# D1_-_No_LCD.net
KiCad netlist of a schematic drawn in EAGLE
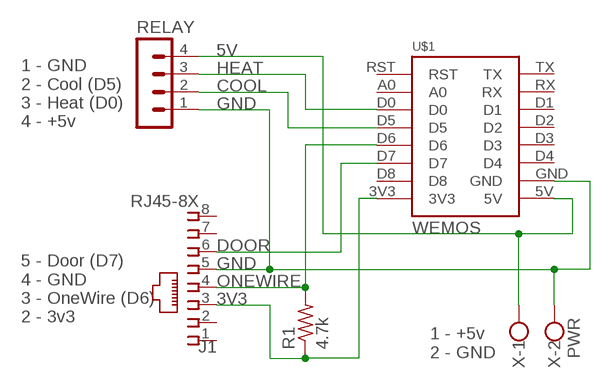
[diagram p0: schematic, sheet 1]

(export (version "E")
  (design (tool "Eeschema 10.0.6"))
  (components
    (comp (ref "J1")
      (value "RJ45-8X")
      (footprint "eagle-import:RJ45-NO-SHIELD")
      (libsource (lib "eagle-import") (part "RJ45-8X"))
    )
    (comp (ref "R1")
      (value "4.7k")
      (footprint "eagle-import:0309_12")
      (libsource (lib "eagle-import") (part "R-US_0309/12"))
    )
    (comp (ref "RELAY")
      (value "MA04-1")
      (footprint "eagle-import:MA04-1")
      (libsource (lib "eagle-import") (part "MA04-1"))
    )
    (comp (ref "U$1")
      (value "WEMOS")
      (footprint "eagle-import:WEMOS")
      (libsource (lib "eagle-import") (part "WEMOS"))
    )
    (comp (ref "X")
      (value "PWR")
      (footprint "eagle-import:W237-102")
      (fields (field (name "MPN") "237-102"))
      (libsource (lib "eagle-import") (part "W237-102"))
    )
  )
  (nets
    (net (code "1") (name "/3V3") (class "Default")
      (node (ref "J1") (pin "3") (pinfunction "3_3") (pintype "passive"))
      (node (ref "R1") (pin "1") (pinfunction "1_1") (pintype "passive"))
      (node (ref "U$1") (pin "3V3") (pinfunction "3V3_3V3") (pintype "bidirectional"))
    )
    (net (code "2") (name "/5V") (class "Default")
      (node (ref "RELAY") (pin "4") (pinfunction "4_4") (pintype "passive"))
      (node (ref "U$1") (pin "5V") (pinfunction "5V_5V") (pintype "bidirectional"))
      (node (ref "X") (pin "1") (pinfunction "KL_1") (pintype "passive"))
    )
    (net (code "3") (name "/COOL") (class "Default")
      (node (ref "RELAY") (pin "2") (pinfunction "2_2") (pintype "passive"))
      (node (ref "U$1") (pin "D5") (pinfunction "D5_D5") (pintype "bidirectional"))
    )
    (net (code "4") (name "/DOOR") (class "Default")
      (node (ref "J1") (pin "6") (pinfunction "6_6") (pintype "passive"))
      (node (ref "U$1") (pin "D7") (pinfunction "D7_D7") (pintype "bidirectional"))
    )
    (net (code "5") (name "/GND") (class "Default")
      (node (ref "J1") (pin "5") (pinfunction "5_5") (pintype "passive"))
      (node (ref "RELAY") (pin "1") (pinfunction "1_1") (pintype "passive"))
      (node (ref "U$1") (pin "GND") (pinfunction "GND_GND") (pintype "bidirectional"))
      (node (ref "X") (pin "2") (pinfunction "KL_2") (pintype "passive"))
    )
    (net (code "6") (name "/HEAT") (class "Default")
      (node (ref "RELAY") (pin "3") (pinfunction "3_3") (pintype "passive"))
      (node (ref "U$1") (pin "D0") (pinfunction "D0_D0") (pintype "bidirectional"))
    )
    (net (code "7") (name "/ONEWIRE") (class "Default")
      (node (ref "J1") (pin "4") (pinfunction "4_4") (pintype "passive"))
      (node (ref "R1") (pin "2") (pinfunction "2_2") (pintype "passive"))
      (node (ref "U$1") (pin "D6") (pinfunction "D6_D6") (pintype "bidirectional"))
    )
    (net (code "8") (name "unconnected-(J1-Pad1)") (class "Default")
      (node (ref "J1") (pin "1") (pinfunction "1_1") (pintype "passive"))
    )
    (net (code "9") (name "unconnected-(J1-Pad2)") (class "Default")
      (node (ref "J1") (pin "2") (pinfunction "2_2") (pintype "passive"))
    )
    (net (code "10") (name "unconnected-(J1-Pad7)") (class "Default")
      (node (ref "J1") (pin "7") (pinfunction "7_7") (pintype "passive"))
    )
    (net (code "11") (name "unconnected-(J1-Pad8)") (class "Default")
      (node (ref "J1") (pin "8") (pinfunction "8_8") (pintype "passive"))
    )
    (net (code "12") (name "unconnected-(U$1-PadA0)") (class "Default")
      (node (ref "U$1") (pin "A0") (pinfunction "A0_A0") (pintype "bidirectional"))
    )
    (net (code "13") (name "unconnected-(U$1-PadD1)") (class "Default")
      (node (ref "U$1") (pin "D1") (pinfunction "D1_D1") (pintype "bidirectional"))
    )
    (net (code "14") (name "unconnected-(U$1-PadD2)") (class "Default")
      (node (ref "U$1") (pin "D2") (pinfunction "D2_D2") (pintype "bidirectional"))
    )
    (net (code "15") (name "unconnected-(U$1-PadD3)") (class "Default")
      (node (ref "U$1") (pin "D3") (pinfunction "D3_D3") (pintype "bidirectional"))
    )
    (net (code "16") (name "unconnected-(U$1-PadD4)") (class "Default")
      (node (ref "U$1") (pin "D4") (pinfunction "D4_D4") (pintype "bidirectional"))
    )
    (net (code "17") (name "unconnected-(U$1-PadD8)") (class "Default")
      (node (ref "U$1") (pin "D8") (pinfunction "D8_D8") (pintype "bidirectional"))
    )
    (net (code "18") (name "unconnected-(U$1-PadRST)") (class "Default")
      (node (ref "U$1") (pin "RST") (pinfunction "RST_RST") (pintype "bidirectional"))
    )
    (net (code "19") (name "unconnected-(U$1-PadRX)") (class "Default")
      (node (ref "U$1") (pin "RX") (pinfunction "RX_RX") (pintype "bidirectional"))
    )
    (net (code "20") (name "unconnected-(U$1-PadTX)") (class "Default")
      (node (ref "U$1") (pin "TX") (pinfunction "TX_TX") (pintype "bidirectional"))
    )
  )
)
